# UPCNSL-ABS-EPS_test-v1_0.net
KiCad netlist of a schematic drawn in Altium Designer
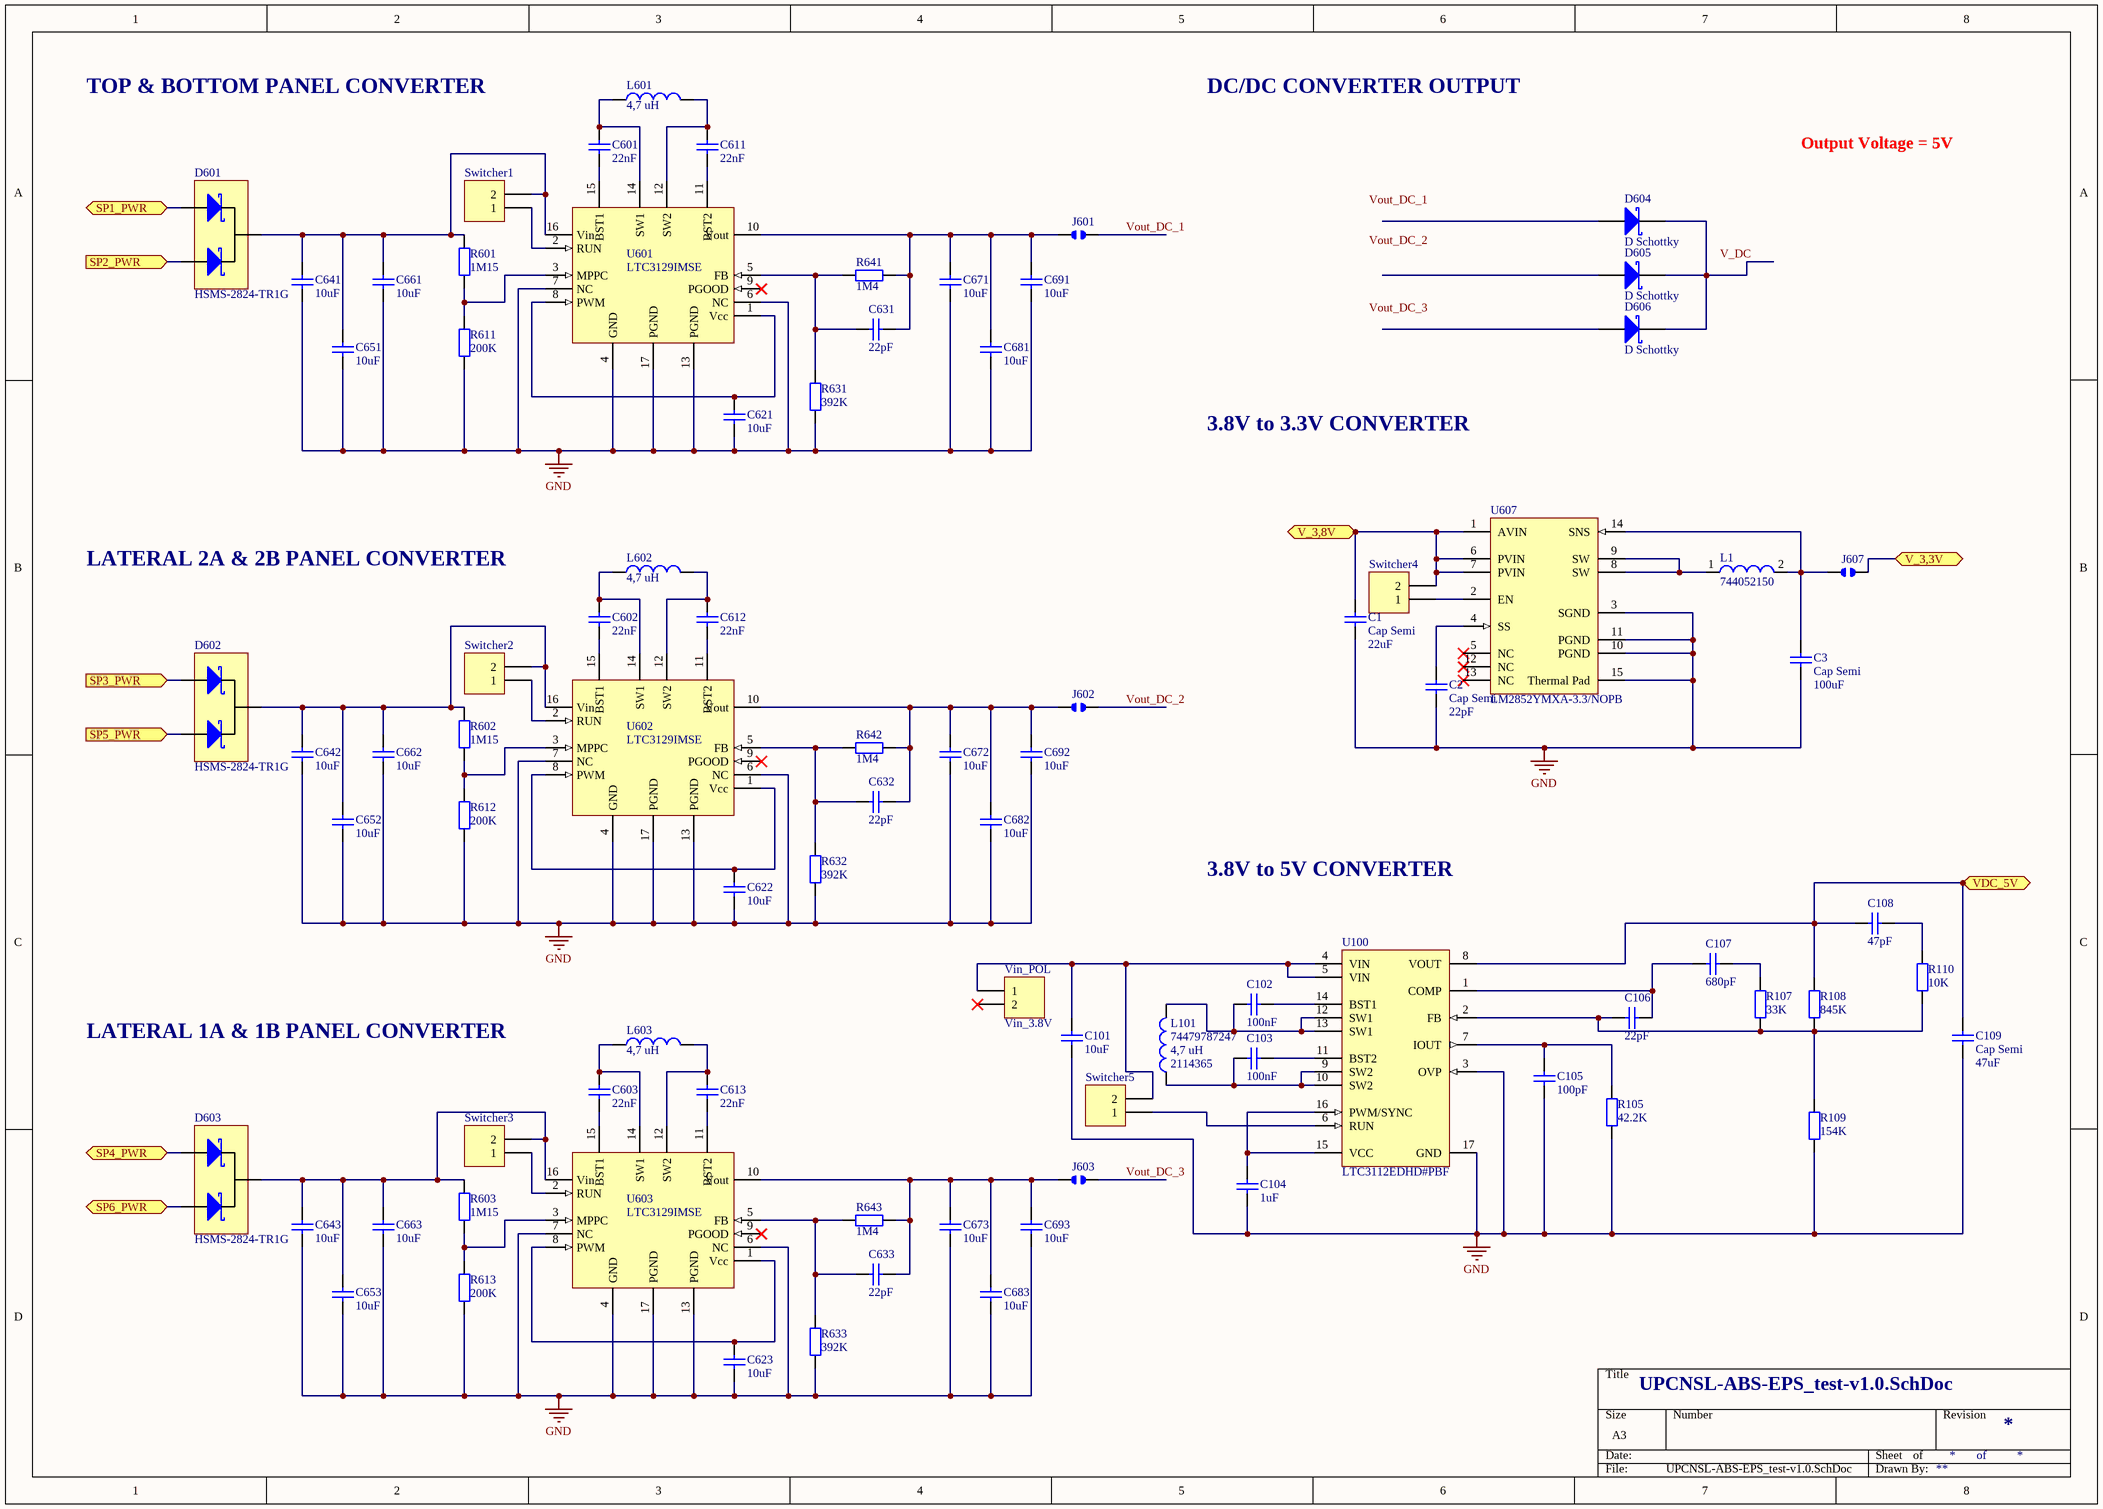
[diagram p0: UPCNSL-ABS-EPS_test-v1.0.SchDoc]

(export (version "E")
  (design (tool "Eeschema 10.0.6"))
  (components
    (comp (ref "C1")
      (value "Cap Semi")
      (footprint "C1206")
      (description "Capacitor (Semiconductor SIM Model)")
      (fields (field (name "ALTIUM_VALUE") "22uF") (field (name "PUBLISHER") "Altium Limited"))
      (libsource (lib "Miscellaneous Devices") (part "Cap Semi"))
    )
    (comp (ref "C2")
      (value "Cap Semi")
      (footprint "1608[0603]")
      (description "Capacitor (Semiconductor SIM Model)")
      (fields (field (name "ALTIUM_VALUE") "22pF") (field (name "PUBLISHER") "Altium Limited"))
      (libsource (lib "Miscellaneous Devices") (part "Cap Semi"))
    )
    (comp (ref "C3")
      (value "Cap Semi")
      (footprint "C1206")
      (description "Capacitor (Semiconductor SIM Model)")
      (fields (field (name "ALTIUM_VALUE") "100uF") (field (name "PUBLISHER") "Altium Limited"))
      (libsource (lib "Miscellaneous Devices") (part "Cap Semi"))
    )
    (comp (ref "C101")
      (value "10uF")
      (footprint "CAP0603")
      (description "Capacitor")
      (fields (field (name "Comment") "CAP0603"))
      (libsource (lib "EPS") (part "CAP0603"))
    )
    (comp (ref "C102")
      (value "100nF")
      (footprint "CAP0603")
      (description "Capacitor")
      (fields (field (name "Comment") "CAP0603"))
      (libsource (lib "EPS") (part "CAP0603"))
    )
    (comp (ref "C103")
      (value "100nF")
      (footprint "CAP0603")
      (description "Capacitor")
      (fields (field (name "Comment") "CAP0603"))
      (libsource (lib "EPS") (part "CAP0603"))
    )
    (comp (ref "C104")
      (value "1uF")
      (footprint "CAP0603")
      (description "Capacitor")
      (fields (field (name "Comment") "CAP0603"))
      (libsource (lib "EPS") (part "CAP0603"))
    )
    (comp (ref "C105")
      (value "100pF")
      (footprint "CAP0603")
      (description "Capacitor")
      (fields (field (name "Comment") "CAP0603"))
      (libsource (lib "EPS") (part "CAP0603"))
    )
    (comp (ref "C106")
      (value "22pF")
      (footprint "CAP0603")
      (description "Capacitor")
      (fields (field (name "Comment") "CAP0603"))
      (libsource (lib "EPS") (part "CAP0603"))
    )
    (comp (ref "C107")
      (value "680pF")
      (footprint "CAP0603")
      (description "Capacitor")
      (fields (field (name "Comment") "CAP0603"))
      (libsource (lib "EPS") (part "CAP0603"))
    )
    (comp (ref "C108")
      (value "47pF")
      (footprint "CAP0603")
      (description "Capacitor")
      (fields (field (name "Comment") "CAP0603"))
      (libsource (lib "EPS") (part "CAP0603"))
    )
    (comp (ref "C109")
      (value "Cap Semi")
      (footprint "C1206")
      (description "Capacitor (Semiconductor SIM Model)")
      (fields (field (name "ALTIUM_VALUE") "47uF") (field (name "PUBLISHER") "Altium Limited"))
      (libsource (lib "Miscellaneous Devices") (part "Cap Semi"))
    )
    (comp (ref "C601")
      (value "22nF")
      (footprint "CAP0603")
      (description "Capacitor")
      (fields (field (name "Comment") "CAP0603"))
      (libsource (lib "EPS") (part "CAP0603"))
    )
    (comp (ref "C602")
      (value "22nF")
      (footprint "CAP0603")
      (description "Capacitor")
      (fields (field (name "Comment") "CAP0603"))
      (libsource (lib "EPS") (part "CAP0603"))
    )
    (comp (ref "C603")
      (value "22nF")
      (footprint "CAP0603")
      (description "Capacitor")
      (fields (field (name "Comment") "CAP0603"))
      (libsource (lib "EPS") (part "CAP0603"))
    )
    (comp (ref "C611")
      (value "22nF")
      (footprint "CAP0603")
      (description "Capacitor")
      (fields (field (name "Comment") "CAP0603"))
      (libsource (lib "EPS") (part "CAP0603"))
    )
    (comp (ref "C612")
      (value "22nF")
      (footprint "CAP0603")
      (description "Capacitor")
      (fields (field (name "Comment") "CAP0603"))
      (libsource (lib "EPS") (part "CAP0603"))
    )
    (comp (ref "C613")
      (value "22nF")
      (footprint "CAP0603")
      (description "Capacitor")
      (fields (field (name "Comment") "CAP0603"))
      (libsource (lib "EPS") (part "CAP0603"))
    )
    (comp (ref "C621")
      (value "10uF")
      (footprint "CAP0603")
      (description "Capacitor")
      (fields (field (name "Comment") "CAP0603"))
      (libsource (lib "EPS") (part "CAP0603"))
    )
    (comp (ref "C622")
      (value "10uF")
      (footprint "CAP0603")
      (description "Capacitor")
      (fields (field (name "Comment") "CAP0603"))
      (libsource (lib "EPS") (part "CAP0603"))
    )
    (comp (ref "C623")
      (value "10uF")
      (footprint "CAP0603")
      (description "Capacitor")
      (fields (field (name "Comment") "CAP0603"))
      (libsource (lib "EPS") (part "CAP0603"))
    )
    (comp (ref "C631")
      (value "22pF")
      (footprint "CAP0603")
      (description "Capacitor")
      (fields (field (name "Comment") "CAP0603"))
      (libsource (lib "EPS") (part "CAP0603"))
    )
    (comp (ref "C632")
      (value "22pF")
      (footprint "CAP0603")
      (description "Capacitor")
      (fields (field (name "Comment") "CAP0603"))
      (libsource (lib "EPS") (part "CAP0603"))
    )
    (comp (ref "C633")
      (value "22pF")
      (footprint "CAP0603")
      (description "Capacitor")
      (fields (field (name "Comment") "CAP0603"))
      (libsource (lib "EPS") (part "CAP0603"))
    )
    (comp (ref "C641")
      (value "10uF")
      (footprint "CAP0603")
      (description "Capacitor")
      (fields (field (name "Comment") "CAP0603"))
      (libsource (lib "EPS") (part "CAP0603"))
    )
    (comp (ref "C642")
      (value "10uF")
      (footprint "CAP0603")
      (description "Capacitor")
      (fields (field (name "Comment") "CAP0603"))
      (libsource (lib "EPS") (part "CAP0603"))
    )
    (comp (ref "C643")
      (value "10uF")
      (footprint "CAP0603")
      (description "Capacitor")
      (fields (field (name "Comment") "CAP0603"))
      (libsource (lib "EPS") (part "CAP0603"))
    )
    (comp (ref "C651")
      (value "10uF")
      (footprint "CAP0603")
      (description "Capacitor")
      (fields (field (name "Comment") "CAP0603"))
      (libsource (lib "EPS") (part "CAP0603"))
    )
    (comp (ref "C652")
      (value "10uF")
      (footprint "CAP0603")
      (description "Capacitor")
      (fields (field (name "Comment") "CAP0603"))
      (libsource (lib "EPS") (part "CAP0603"))
    )
    (comp (ref "C653")
      (value "10uF")
      (footprint "CAP0603")
      (description "Capacitor")
      (fields (field (name "Comment") "CAP0603"))
      (libsource (lib "EPS") (part "CAP0603"))
    )
    (comp (ref "C661")
      (value "10uF")
      (footprint "CAP0603")
      (description "Capacitor")
      (fields (field (name "Comment") "CAP0603"))
      (libsource (lib "EPS") (part "CAP0603"))
    )
    (comp (ref "C662")
      (value "10uF")
      (footprint "CAP0603")
      (description "Capacitor")
      (fields (field (name "Comment") "CAP0603"))
      (libsource (lib "EPS") (part "CAP0603"))
    )
    (comp (ref "C663")
      (value "10uF")
      (footprint "CAP0603")
      (description "Capacitor")
      (fields (field (name "Comment") "CAP0603"))
      (libsource (lib "EPS") (part "CAP0603"))
    )
    (comp (ref "C671")
      (value "10uF")
      (footprint "CAP0603")
      (description "Capacitor")
      (fields (field (name "Comment") "CAP0603"))
      (libsource (lib "EPS") (part "CAP0603"))
    )
    (comp (ref "C672")
      (value "10uF")
      (footprint "CAP0603")
      (description "Capacitor")
      (fields (field (name "Comment") "CAP0603"))
      (libsource (lib "EPS") (part "CAP0603"))
    )
    (comp (ref "C673")
      (value "10uF")
      (footprint "CAP0603")
      (description "Capacitor")
      (fields (field (name "Comment") "CAP0603"))
      (libsource (lib "EPS") (part "CAP0603"))
    )
    (comp (ref "C681")
      (value "10uF")
      (footprint "CAP0603")
      (description "Capacitor")
      (fields (field (name "Comment") "CAP0603"))
      (libsource (lib "EPS") (part "CAP0603"))
    )
    (comp (ref "C682")
      (value "10uF")
      (footprint "CAP0603")
      (description "Capacitor")
      (fields (field (name "Comment") "CAP0603"))
      (libsource (lib "EPS") (part "CAP0603"))
    )
    (comp (ref "C683")
      (value "10uF")
      (footprint "CAP0603")
      (description "Capacitor")
      (fields (field (name "Comment") "CAP0603"))
      (libsource (lib "EPS") (part "CAP0603"))
    )
    (comp (ref "C691")
      (value "10uF")
      (footprint "CAP0603")
      (description "Capacitor")
      (fields (field (name "Comment") "CAP0603"))
      (libsource (lib "EPS") (part "CAP0603"))
    )
    (comp (ref "C692")
      (value "10uF")
      (footprint "CAP0603")
      (description "Capacitor")
      (fields (field (name "Comment") "CAP0603"))
      (libsource (lib "EPS") (part "CAP0603"))
    )
    (comp (ref "C693")
      (value "10uF")
      (footprint "CAP0603")
      (description "Capacitor")
      (fields (field (name "Comment") "CAP0603"))
      (libsource (lib "EPS") (part "CAP0603"))
    )
    (comp (ref "D601")
      (value "HSMS-2824-TR1G")
      (footprint "SOT23-3")
      (description "DIODE, RF, SCHOTTKY, DUAL, SOT-23")
      (libsource (lib "EPS") (part "HSMS-2824-TR1G"))
    )
    (comp (ref "D602")
      (value "HSMS-2824-TR1G")
      (footprint "SOT23-3")
      (description "DIODE, RF, SCHOTTKY, DUAL, SOT-23")
      (libsource (lib "EPS") (part "HSMS-2824-TR1G"))
    )
    (comp (ref "D603")
      (value "HSMS-2824-TR1G")
      (footprint "SOT23-3")
      (description "DIODE, RF, SCHOTTKY, DUAL, SOT-23")
      (libsource (lib "EPS") (part "HSMS-2824-TR1G"))
    )
    (comp (ref "D604")
      (value "D Schottky")
      (footprint "SMB")
      (description "Schottky Diode")
      (fields (field (name "PUBLISHER") "Altium Limited"))
      (libsource (lib "Miscellaneous Devices") (part "D Schottky"))
    )
    (comp (ref "D605")
      (value "D Schottky")
      (footprint "SMB")
      (description "Schottky Diode")
      (fields (field (name "PUBLISHER") "Altium Limited"))
      (libsource (lib "Miscellaneous Devices") (part "D Schottky"))
    )
    (comp (ref "D606")
      (value "D Schottky")
      (footprint "SMB")
      (description "Schottky Diode")
      (fields (field (name "PUBLISHER") "Altium Limited"))
      (libsource (lib "Miscellaneous Devices") (part "D Schottky"))
    )
    (comp (ref "J601")
      (value "Jumper_Solderpad")
      (footprint "JUMPER_SOLDERPAD")
      (libsource (lib "EPS") (part "Jumper_Solderpad"))
    )
    (comp (ref "J602")
      (value "Jumper_Solderpad")
      (footprint "JUMPER_SOLDERPAD")
      (libsource (lib "EPS") (part "Jumper_Solderpad"))
    )
    (comp (ref "J603")
      (value "Jumper_Solderpad")
      (footprint "JUMPER_SOLDERPAD")
      (libsource (lib "EPS") (part "Jumper_Solderpad"))
    )
    (comp (ref "J607")
      (value "~")
      (footprint "JUMPER_SOLDERPAD")
      (description "Jumper_Solderpad")
      (libsource (lib "EPS") (part "Jumper_Solderpad"))
    )
    (comp (ref "L1")
      (value "744052150")
      (footprint "WE-TPC-5818-L")
      (description "SMD Shielded Tiny Power Inductor WE-TPC, L = 15.0 µH")
      (libsource (lib "WE-TPC SMD Shielded Tiny Power Inductor") (part "744052150"))
    )
    (comp (ref "L101")
      (value "74479787247")
      (footprint "74479787247")
      (description "INDUCTOR, 4.7UH, 1.25A, 40MHZ")
      (fields (field (name "ALTIUM_VALUE") "4,7 uH") (field (name "SUPPLIER PART NUMBER 1") "2114365"))
      (libsource (lib "EPS") (part "74479787247"))
    )
    (comp (ref "L601")
      (value "4,7 uH")
      (footprint "74479787247")
      (description "INDUCTOR, 4.7UH, 1.25A, 40MHZ")
      (libsource (lib "EPS") (part "74479787247"))
    )
    (comp (ref "L602")
      (value "4,7 uH")
      (footprint "74479787247")
      (description "INDUCTOR, 4.7UH, 1.25A, 40MHZ")
      (libsource (lib "EPS") (part "74479787247"))
    )
    (comp (ref "L603")
      (value "4,7 uH")
      (footprint "74479787247")
      (description "INDUCTOR, 4.7UH, 1.25A, 40MHZ")
      (libsource (lib "EPS") (part "74479787247"))
    )
    (comp (ref "R105")
      (value "42.2K")
      (footprint "RES0603")
      (description "Resistor")
      (fields (field (name "Comment") "RES0603"))
      (libsource (lib "EPS") (part "RES0603"))
    )
    (comp (ref "R107")
      (value "33K")
      (footprint "RES0603")
      (description "Resistor")
      (fields (field (name "Comment") "RES0603"))
      (libsource (lib "EPS") (part "RES0603"))
    )
    (comp (ref "R108")
      (value "845K")
      (footprint "RES0603")
      (description "Resistor")
      (fields (field (name "Comment") "RES0603"))
      (libsource (lib "EPS") (part "RES0603"))
    )
    (comp (ref "R109")
      (value "154K")
      (footprint "RES0603")
      (description "Resistor")
      (fields (field (name "Comment") "RES0603"))
      (libsource (lib "EPS") (part "RES0603"))
    )
    (comp (ref "R110")
      (value "10K")
      (footprint "RES0603")
      (description "Resistor")
      (fields (field (name "Comment") "RES0603"))
      (libsource (lib "EPS") (part "RES0603"))
    )
    (comp (ref "R601")
      (value "1M15")
      (footprint "RES0603")
      (description "Resistor")
      (fields (field (name "Comment") "RES0603"))
      (libsource (lib "EPS") (part "RES0603"))
    )
    (comp (ref "R602")
      (value "1M15")
      (footprint "RES0603")
      (description "Resistor")
      (fields (field (name "Comment") "RES0603"))
      (libsource (lib "EPS") (part "RES0603"))
    )
    (comp (ref "R603")
      (value "1M15")
      (footprint "RES0603")
      (description "Resistor")
      (fields (field (name "Comment") "RES0603"))
      (libsource (lib "EPS") (part "RES0603"))
    )
    (comp (ref "R611")
      (value "200K")
      (footprint "RES0603")
      (description "Resistor")
      (fields (field (name "Comment") "RES0603"))
      (libsource (lib "EPS") (part "RES0603"))
    )
    (comp (ref "R612")
      (value "200K")
      (footprint "RES0603")
      (description "Resistor")
      (fields (field (name "Comment") "RES0603"))
      (libsource (lib "EPS") (part "RES0603"))
    )
    (comp (ref "R613")
      (value "200K")
      (footprint "RES0603")
      (description "Resistor")
      (fields (field (name "Comment") "RES0603"))
      (libsource (lib "EPS") (part "RES0603"))
    )
    (comp (ref "R631")
      (value "392K")
      (footprint "RES0603")
      (description "Resistor")
      (fields (field (name "Comment") "RES0603"))
      (libsource (lib "EPS") (part "RES0603"))
    )
    (comp (ref "R632")
      (value "392K")
      (footprint "RES0603")
      (description "Resistor")
      (fields (field (name "Comment") "RES0603"))
      (libsource (lib "EPS") (part "RES0603"))
    )
    (comp (ref "R633")
      (value "392K")
      (footprint "RES0603")
      (description "Resistor")
      (fields (field (name "Comment") "RES0603"))
      (libsource (lib "EPS") (part "RES0603"))
    )
    (comp (ref "R641")
      (value "1M4")
      (footprint "RES0603")
      (description "Resistor")
      (fields (field (name "Comment") "RES0603"))
      (libsource (lib "") (part "RES0603_1"))
    )
    (comp (ref "R642")
      (value "1M4")
      (footprint "RES0603")
      (description "Resistor")
      (fields (field (name "Comment") "RES0603"))
      (libsource (lib "") (part "RES0603_1"))
    )
    (comp (ref "R643")
      (value "1M4")
      (footprint "RES0603")
      (description "Resistor")
      (fields (field (name "Comment") "RES0603"))
      (libsource (lib "") (part "RES0603_1"))
    )
    (comp (ref "Switcher1")
      (value "~")
      (footprint "HDR1X2")
      (description "Header, 2-Pin")
      (fields (field (name "PUBLISHER") "Altium Limited"))
      (libsource (lib "Miscellaneous Connectors") (part "Header 2"))
    )
    (comp (ref "Switcher2")
      (value "~")
      (footprint "HDR1X2")
      (description "Header, 2-Pin")
      (fields (field (name "PUBLISHER") "Altium Limited"))
      (libsource (lib "Miscellaneous Connectors") (part "Header 2"))
    )
    (comp (ref "Switcher3")
      (value "~")
      (footprint "HDR1X2")
      (description "Header, 2-Pin")
      (fields (field (name "PUBLISHER") "Altium Limited"))
      (libsource (lib "Miscellaneous Connectors") (part "Header 2"))
    )
    (comp (ref "Switcher4")
      (value "~")
      (footprint "HDR1X2")
      (description "Header, 2-Pin")
      (fields (field (name "PUBLISHER") "Altium Limited"))
      (libsource (lib "Miscellaneous Connectors") (part "Header 2"))
    )
    (comp (ref "Switcher5")
      (value "~")
      (footprint "HDR1X2")
      (description "Header, 2-Pin")
      (fields (field (name "PUBLISHER") "Altium Limited"))
      (libsource (lib "Miscellaneous Connectors") (part "Header 2"))
    )
    (comp (ref "U100")
      (value "LTC3112EDHD#PBF")
      (footprint "LT-DHD-16_V")
      (description "2.5 A Synchronous Buck-Boost DC/DC Converter, 16-pin SON (DHD-16), -40 to 125 degC, Pb-Free")
      (fields (field (name "MANUFACTURER") "Linear Technology"))
      (libsource (lib "Linear Technology Power Management Switching Regulator LTC1174-LTC3901") (part "LTC3112EDHD#PBF"))
    )
    (comp (ref "U601")
      (value "LTC3129IMSE")
      (footprint "MSOP-16")
      (description "15V, 200mA Synchronous Buck-Boost DC/DC Converter with 1.3µA Quiescent Current")
      (libsource (lib "EPS") (part "LTC3129"))
    )
    (comp (ref "U602")
      (value "LTC3129IMSE")
      (footprint "MSOP-16")
      (description "15V, 200mA Synchronous Buck-Boost DC/DC Converter with 1.3µA Quiescent Current")
      (libsource (lib "EPS") (part "LTC3129"))
    )
    (comp (ref "U603")
      (value "LTC3129IMSE")
      (footprint "MSOP-16")
      (description "15V, 200mA Synchronous Buck-Boost DC/DC Converter with 1.3µA Quiescent Current")
      (libsource (lib "EPS") (part "LTC3129"))
    )
    (comp (ref "U607")
      (value "LM2852YMXA-3.3/NOPB")
      (footprint "MXA14A_L")
      (description "2A 500/1500kHz Synchronous SIMPLE SWITCHER® Buck Regulator, 14-pin TSSOP-EP, Pb-Free")
      (fields (field (name "MANUFACTURER") "National Semiconductor"))
      (libsource (lib "Switcher") (part "LM2852YMXA-3.3/NOPB"))
    )
    (comp (ref "Vin_POL")
      (value "Vin_3.8V")
      (footprint "HDR1X2")
      (description "Header, 2-Pin")
      (fields (field (name "PUBLISHER") "Altium Limited"))
      (libsource (lib "") (part "Header 2_1"))
    )
  )
  (nets
    (net (code "1") (name "/SP1_PWR") (class "Default")
      (node (ref "D601") (pin "1") (pinfunction "A1_1") (pintype "passive"))
    )
    (net (code "2") (name "/SP2_PWR") (class "Default")
      (node (ref "D601") (pin "2") (pinfunction "A2_2") (pintype "passive"))
    )
    (net (code "3") (name "/SP3_PWR") (class "Default")
      (node (ref "D602") (pin "1") (pinfunction "A1_1") (pintype "passive"))
    )
    (net (code "4") (name "/SP4_PWR") (class "Default")
      (node (ref "D603") (pin "1") (pinfunction "A1_1") (pintype "passive"))
    )
    (net (code "5") (name "/SP5_PWR") (class "Default")
      (node (ref "D602") (pin "2") (pinfunction "A2_2") (pintype "passive"))
    )
    (net (code "6") (name "/SP6_PWR") (class "Default")
      (node (ref "D603") (pin "2") (pinfunction "A2_2") (pintype "passive"))
    )
    (net (code "7") (name "/VDC_5V") (class "Default")
      (node (ref "C108") (pin "1") (pinfunction "1_1") (pintype "passive"))
      (node (ref "C109") (pin "1") (pinfunction "1_1") (pintype "passive"))
      (node (ref "R108") (pin "2") (pinfunction "2_2") (pintype "passive"))
      (node (ref "U100") (pin "8") (pinfunction "VOUT_8") (pintype "power_in"))
    )
    (net (code "8") (name "/V_3,3V") (class "Default")
      (node (ref "J607") (pin "2") (pinfunction "2_2") (pintype "passive"))
    )
    (net (code "9") (name "/V_3,8V") (class "Default")
      (node (ref "C1") (pin "1") (pinfunction "1_1") (pintype "passive"))
      (node (ref "Switcher4") (pin "2") (pinfunction "2_2") (pintype "passive"))
      (node (ref "U607") (pin "1") (pinfunction "AVIN_1") (pintype "power_in"))
      (node (ref "U607") (pin "6") (pinfunction "PVIN_6") (pintype "power_in"))
      (node (ref "U607") (pin "7") (pinfunction "PVIN_7") (pintype "power_in"))
    )
    (net (code "11") (name "/Vout_DC_1") (class "Default")
      (node (ref "J601") (pin "2") (pinfunction "2_2") (pintype "passive"))
    )
    (net (code "12") (name "/Vout_DC_2") (class "Default")
      (node (ref "J602") (pin "2") (pinfunction "2_2") (pintype "passive"))
    )
    (net (code "13") (name "/Vout_DC_3") (class "Default")
      (node (ref "J603") (pin "2") (pinfunction "2_2") (pintype "passive"))
    )
    (net (code "14") (name "GND") (class "Default")
      (node (ref "C1") (pin "2") (pinfunction "2_2") (pintype "passive"))
      (node (ref "C101") (pin "1") (pinfunction "1_1") (pintype "passive"))
      (node (ref "C104") (pin "1") (pinfunction "1_1") (pintype "passive"))
      (node (ref "C105") (pin "1") (pinfunction "1_1") (pintype "passive"))
      (node (ref "C109") (pin "2") (pinfunction "2_2") (pintype "passive"))
      (node (ref "C2") (pin "2") (pinfunction "2_2") (pintype "passive"))
      (node (ref "C3") (pin "2") (pinfunction "2_2") (pintype "passive"))
      (node (ref "C621") (pin "1") (pinfunction "1_1") (pintype "passive"))
      (node (ref "C622") (pin "1") (pinfunction "1_1") (pintype "passive"))
      (node (ref "C623") (pin "1") (pinfunction "1_1") (pintype "passive"))
      (node (ref "C641") (pin "1") (pinfunction "1_1") (pintype "passive"))
      (node (ref "C642") (pin "1") (pinfunction "1_1") (pintype "passive"))
      (node (ref "C643") (pin "1") (pinfunction "1_1") (pintype "passive"))
      (node (ref "C651") (pin "1") (pinfunction "1_1") (pintype "passive"))
      (node (ref "C652") (pin "1") (pinfunction "1_1") (pintype "passive"))
      (node (ref "C653") (pin "1") (pinfunction "1_1") (pintype "passive"))
      (node (ref "C661") (pin "1") (pinfunction "1_1") (pintype "passive"))
      (node (ref "C662") (pin "1") (pinfunction "1_1") (pintype "passive"))
      (node (ref "C663") (pin "1") (pinfunction "1_1") (pintype "passive"))
      (node (ref "C671") (pin "1") (pinfunction "1_1") (pintype "passive"))
      (node (ref "C672") (pin "1") (pinfunction "1_1") (pintype "passive"))
      (node (ref "C673") (pin "1") (pinfunction "1_1") (pintype "passive"))
      (node (ref "C681") (pin "1") (pinfunction "1_1") (pintype "passive"))
      (node (ref "C682") (pin "1") (pinfunction "1_1") (pintype "passive"))
      (node (ref "C683") (pin "1") (pinfunction "1_1") (pintype "passive"))
      (node (ref "C691") (pin "1") (pinfunction "1_1") (pintype "passive"))
      (node (ref "C692") (pin "1") (pinfunction "1_1") (pintype "passive"))
      (node (ref "C693") (pin "1") (pinfunction "1_1") (pintype "passive"))
      (node (ref "R105") (pin "1") (pinfunction "1_1") (pintype "passive"))
      (node (ref "R109") (pin "1") (pinfunction "1_1") (pintype "passive"))
      (node (ref "R611") (pin "1") (pinfunction "1_1") (pintype "passive"))
      (node (ref "R612") (pin "1") (pinfunction "1_1") (pintype "passive"))
      (node (ref "R613") (pin "1") (pinfunction "1_1") (pintype "passive"))
      (node (ref "R631") (pin "1") (pinfunction "1_1") (pintype "passive"))
      (node (ref "R632") (pin "1") (pinfunction "1_1") (pintype "passive"))
      (node (ref "R633") (pin "1") (pinfunction "1_1") (pintype "passive"))
      (node (ref "U100") (pin "17") (pinfunction "GND_17") (pintype "power_in"))
      (node (ref "U100") (pin "3") (pinfunction "OVP_3") (pintype "input"))
      (node (ref "U601") (pin "13") (pinfunction "PGND_13") (pintype "power_in"))
      (node (ref "U601") (pin "17") (pinfunction "PGND_17") (pintype "power_in"))
      (node (ref "U601") (pin "4") (pinfunction "GND_4") (pintype "power_in"))
      (node (ref "U601") (pin "6") (pinfunction "NC_6") (pintype "passive"))
      (node (ref "U601") (pin "7") (pinfunction "NC_7") (pintype "passive"))
      (node (ref "U602") (pin "13") (pinfunction "PGND_13") (pintype "power_in"))
      (node (ref "U602") (pin "17") (pinfunction "PGND_17") (pintype "power_in"))
      (node (ref "U602") (pin "4") (pinfunction "GND_4") (pintype "power_in"))
      (node (ref "U602") (pin "6") (pinfunction "NC_6") (pintype "passive"))
      (node (ref "U602") (pin "7") (pinfunction "NC_7") (pintype "passive"))
      (node (ref "U603") (pin "13") (pinfunction "PGND_13") (pintype "power_in"))
      (node (ref "U603") (pin "17") (pinfunction "PGND_17") (pintype "power_in"))
      (node (ref "U603") (pin "4") (pinfunction "GND_4") (pintype "power_in"))
      (node (ref "U603") (pin "6") (pinfunction "NC_6") (pintype "passive"))
      (node (ref "U603") (pin "7") (pinfunction "NC_7") (pintype "passive"))
      (node (ref "U607") (pin "10") (pinfunction "PGND_10") (pintype "power_in"))
      (node (ref "U607") (pin "11") (pinfunction "PGND_11") (pintype "power_in"))
      (node (ref "U607") (pin "15") (pinfunction "Thermal_Pad_15") (pintype "power_in"))
      (node (ref "U607") (pin "3") (pinfunction "SGND_3") (pintype "power_in"))
    )
    (net (code "15") (name "Net-(C101-Pad2)") (class "Default")
      (node (ref "C101") (pin "2") (pinfunction "2_2") (pintype "passive"))
      (node (ref "Switcher5") (pin "2") (pinfunction "2_2") (pintype "passive"))
      (node (ref "U100") (pin "4") (pinfunction "VIN_4") (pintype "power_in"))
      (node (ref "U100") (pin "5") (pinfunction "VIN_5") (pintype "power_in"))
      (node (ref "Vin_POL") (pin "1") (pinfunction "1_1") (pintype "passive"))
    )
    (net (code "16") (name "Net-(C102-Pad2)") (class "Default")
      (node (ref "C102") (pin "2") (pinfunction "2_2") (pintype "passive"))
      (node (ref "L101") (pin "2") (pinfunction "2_2") (pintype "passive"))
      (node (ref "U100") (pin "12") (pinfunction "SW1_12") (pintype "passive"))
      (node (ref "U100") (pin "13") (pinfunction "SW1_13") (pintype "passive"))
    )
    (net (code "17") (name "Net-(C103-Pad2)") (class "Default")
      (node (ref "C103") (pin "2") (pinfunction "2_2") (pintype "passive"))
      (node (ref "L101") (pin "1") (pinfunction "1_1") (pintype "passive"))
      (node (ref "U100") (pin "10") (pinfunction "SW2_10") (pintype "passive"))
      (node (ref "U100") (pin "9") (pinfunction "SW2_9") (pintype "passive"))
    )
    (net (code "18") (name "Net-(C107-Pad2)") (class "Default")
      (node (ref "C107") (pin "2") (pinfunction "2_2") (pintype "passive"))
      (node (ref "R107") (pin "2") (pinfunction "2_2") (pintype "passive"))
    )
    (net (code "19") (name "Net-(C108-Pad2)") (class "Default")
      (node (ref "C108") (pin "2") (pinfunction "2_2") (pintype "passive"))
      (node (ref "R110") (pin "2") (pinfunction "2_2") (pintype "passive"))
    )
    (net (code "20") (name "Net-(D601-K)") (class "Default")
      (node (ref "C641") (pin "2") (pinfunction "2_2") (pintype "passive"))
      (node (ref "C651") (pin "2") (pinfunction "2_2") (pintype "passive"))
      (node (ref "C661") (pin "2") (pinfunction "2_2") (pintype "passive"))
      (node (ref "D601") (pin "3") (pinfunction "K_3") (pintype "passive"))
      (node (ref "R601") (pin "2") (pinfunction "2_2") (pintype "passive"))
      (node (ref "Switcher1") (pin "2") (pinfunction "2_2") (pintype "passive"))
      (node (ref "U601") (pin "16") (pinfunction "Vin_16") (pintype "power_in"))
    )
    (net (code "21") (name "Net-(D602-K)") (class "Default")
      (node (ref "C642") (pin "2") (pinfunction "2_2") (pintype "passive"))
      (node (ref "C652") (pin "2") (pinfunction "2_2") (pintype "passive"))
      (node (ref "C662") (pin "2") (pinfunction "2_2") (pintype "passive"))
      (node (ref "D602") (pin "3") (pinfunction "K_3") (pintype "passive"))
      (node (ref "R602") (pin "2") (pinfunction "2_2") (pintype "passive"))
      (node (ref "Switcher2") (pin "2") (pinfunction "2_2") (pintype "passive"))
      (node (ref "U602") (pin "16") (pinfunction "Vin_16") (pintype "power_in"))
    )
    (net (code "22") (name "Net-(D603-K)") (class "Default")
      (node (ref "C643") (pin "2") (pinfunction "2_2") (pintype "passive"))
      (node (ref "C653") (pin "2") (pinfunction "2_2") (pintype "passive"))
      (node (ref "C663") (pin "2") (pinfunction "2_2") (pintype "passive"))
      (node (ref "D603") (pin "3") (pinfunction "K_3") (pintype "passive"))
      (node (ref "R603") (pin "2") (pinfunction "2_2") (pintype "passive"))
      (node (ref "Switcher3") (pin "2") (pinfunction "2_2") (pintype "passive"))
      (node (ref "U603") (pin "16") (pinfunction "Vin_16") (pintype "power_in"))
    )
    (net (code "23") (name "Net-(D604-K)") (class "Default")
      (node (ref "D604") (pin "2") (pinfunction "K_2") (pintype "passive"))
      (node (ref "D605") (pin "2") (pinfunction "K_2") (pintype "passive"))
      (node (ref "D606") (pin "2") (pinfunction "K_2") (pintype "passive"))
    )
    (net (code "24") (name "Net-(L1-Pad1)") (class "Default")
      (node (ref "L1") (pin "1") (pinfunction "1_1") (pintype "passive"))
      (node (ref "U607") (pin "8") (pinfunction "SW_8") (pintype "power_in"))
      (node (ref "U607") (pin "9") (pinfunction "SW_9") (pintype "power_in"))
    )
    (net (code "25") (name "Net-(U100-BST1)") (class "Default")
      (node (ref "C102") (pin "1") (pinfunction "1_1") (pintype "passive"))
      (node (ref "U100") (pin "14") (pinfunction "BST1_14") (pintype "passive"))
    )
    (net (code "26") (name "Net-(U100-BST2)") (class "Default")
      (node (ref "C103") (pin "1") (pinfunction "1_1") (pintype "passive"))
      (node (ref "U100") (pin "11") (pinfunction "BST2_11") (pintype "passive"))
    )
    (net (code "27") (name "Net-(U100-COMP)") (class "Default")
      (node (ref "C106") (pin "2") (pinfunction "2_2") (pintype "passive"))
      (node (ref "C107") (pin "1") (pinfunction "1_1") (pintype "passive"))
      (node (ref "U100") (pin "1") (pinfunction "COMP_1") (pintype "passive"))
    )
    (net (code "28") (name "Net-(U100-FB)") (class "Default")
      (node (ref "C106") (pin "1") (pinfunction "1_1") (pintype "passive"))
      (node (ref "R107") (pin "1") (pinfunction "1_1") (pintype "passive"))
      (node (ref "R108") (pin "1") (pinfunction "1_1") (pintype "passive"))
      (node (ref "R109") (pin "2") (pinfunction "2_2") (pintype "passive"))
      (node (ref "R110") (pin "1") (pinfunction "1_1") (pintype "passive"))
      (node (ref "U100") (pin "2") (pinfunction "FB_2") (pintype "input"))
    )
    (net (code "29") (name "Net-(U100-IOUT)") (class "Default")
      (node (ref "C105") (pin "2") (pinfunction "2_2") (pintype "passive"))
      (node (ref "R105") (pin "2") (pinfunction "2_2") (pintype "passive"))
      (node (ref "U100") (pin "7") (pinfunction "IOUT_7") (pintype "output"))
    )
    (net (code "30") (name "Net-(U100-PWM{slash}SYNC)") (class "Default")
      (node (ref "C104") (pin "2") (pinfunction "2_2") (pintype "passive"))
      (node (ref "U100") (pin "15") (pinfunction "VCC_15") (pintype "power_in"))
      (node (ref "U100") (pin "16") (pinfunction "PWM/SYNC_16") (pintype "input"))
    )
    (net (code "31") (name "Net-(U100-RUN)") (class "Default")
      (node (ref "Switcher5") (pin "1") (pinfunction "1_1") (pintype "passive"))
      (node (ref "U100") (pin "6") (pinfunction "RUN_6") (pintype "input"))
    )
    (net (code "32") (name "Net-(U601-BST1)") (class "Default")
      (node (ref "C601") (pin "1") (pinfunction "1_1") (pintype "passive"))
      (node (ref "U601") (pin "15") (pinfunction "BST1_15") (pintype "power_in"))
    )
    (net (code "33") (name "Net-(U601-BST2)") (class "Default")
      (node (ref "C611") (pin "1") (pinfunction "1_1") (pintype "passive"))
      (node (ref "U601") (pin "11") (pinfunction "BST2_11") (pintype "power_in"))
    )
    (net (code "34") (name "Net-(U601-FB)") (class "Default")
      (node (ref "C631") (pin "2") (pinfunction "2_2") (pintype "passive"))
      (node (ref "R631") (pin "2") (pinfunction "2_2") (pintype "passive"))
      (node (ref "R641") (pin "2") (pinfunction "2_2") (pintype "passive"))
      (node (ref "U601") (pin "5") (pinfunction "FB_5") (pintype "input"))
    )
    (net (code "35") (name "Net-(U601-MPPC)") (class "Default")
      (node (ref "R601") (pin "1") (pinfunction "1_1") (pintype "passive"))
      (node (ref "R611") (pin "2") (pinfunction "2_2") (pintype "passive"))
      (node (ref "U601") (pin "3") (pinfunction "MPPC_3") (pintype "input"))
    )
    (net (code "36") (name "Net-(U601-PWM)") (class "Default")
      (node (ref "C621") (pin "2") (pinfunction "2_2") (pintype "passive"))
      (node (ref "U601") (pin "1") (pinfunction "Vcc_1") (pintype "power_in"))
      (node (ref "U601") (pin "8") (pinfunction "PWM_8") (pintype "input"))
    )
    (net (code "37") (name "Net-(U601-RUN)") (class "Default")
      (node (ref "Switcher1") (pin "1") (pinfunction "1_1") (pintype "passive"))
      (node (ref "U601") (pin "2") (pinfunction "RUN_2") (pintype "input"))
    )
    (net (code "38") (name "Net-(U601-SW1)") (class "Default")
      (node (ref "C601") (pin "2") (pinfunction "2_2") (pintype "passive"))
      (node (ref "L601") (pin "1") (pinfunction "1_1") (pintype "passive"))
      (node (ref "U601") (pin "14") (pinfunction "SW1_14") (pintype "power_in"))
    )
    (net (code "39") (name "Net-(U601-SW2)") (class "Default")
      (node (ref "C611") (pin "2") (pinfunction "2_2") (pintype "passive"))
      (node (ref "L601") (pin "2") (pinfunction "2_2") (pintype "passive"))
      (node (ref "U601") (pin "12") (pinfunction "SW2_12") (pintype "power_in"))
    )
    (net (code "40") (name "Net-(U601-Vout)") (class "Default")
      (node (ref "C631") (pin "1") (pinfunction "1_1") (pintype "passive"))
      (node (ref "C671") (pin "2") (pinfunction "2_2") (pintype "passive"))
      (node (ref "C681") (pin "2") (pinfunction "2_2") (pintype "passive"))
      (node (ref "C691") (pin "2") (pinfunction "2_2") (pintype "passive"))
      (node (ref "J601") (pin "1") (pinfunction "1_1") (pintype "passive"))
      (node (ref "R641") (pin "1") (pinfunction "1_1") (pintype "passive"))
      (node (ref "U601") (pin "10") (pinfunction "Vout_10") (pintype "power_in"))
    )
    (net (code "41") (name "Net-(U602-BST1)") (class "Default")
      (node (ref "C602") (pin "1") (pinfunction "1_1") (pintype "passive"))
      (node (ref "U602") (pin "15") (pinfunction "BST1_15") (pintype "power_in"))
    )
    (net (code "42") (name "Net-(U602-BST2)") (class "Default")
      (node (ref "C612") (pin "1") (pinfunction "1_1") (pintype "passive"))
      (node (ref "U602") (pin "11") (pinfunction "BST2_11") (pintype "power_in"))
    )
    (net (code "43") (name "Net-(U602-FB)") (class "Default")
      (node (ref "C632") (pin "2") (pinfunction "2_2") (pintype "passive"))
      (node (ref "R632") (pin "2") (pinfunction "2_2") (pintype "passive"))
      (node (ref "R642") (pin "2") (pinfunction "2_2") (pintype "passive"))
      (node (ref "U602") (pin "5") (pinfunction "FB_5") (pintype "input"))
    )
    (net (code "44") (name "Net-(U602-MPPC)") (class "Default")
      (node (ref "R602") (pin "1") (pinfunction "1_1") (pintype "passive"))
      (node (ref "R612") (pin "2") (pinfunction "2_2") (pintype "passive"))
      (node (ref "U602") (pin "3") (pinfunction "MPPC_3") (pintype "input"))
    )
    (net (code "45") (name "Net-(U602-PWM)") (class "Default")
      (node (ref "C622") (pin "2") (pinfunction "2_2") (pintype "passive"))
      (node (ref "U602") (pin "1") (pinfunction "Vcc_1") (pintype "power_in"))
      (node (ref "U602") (pin "8") (pinfunction "PWM_8") (pintype "input"))
    )
    (net (code "46") (name "Net-(U602-RUN)") (class "Default")
      (node (ref "Switcher2") (pin "1") (pinfunction "1_1") (pintype "passive"))
      (node (ref "U602") (pin "2") (pinfunction "RUN_2") (pintype "input"))
    )
    (net (code "47") (name "Net-(U602-SW1)") (class "Default")
      (node (ref "C602") (pin "2") (pinfunction "2_2") (pintype "passive"))
      (node (ref "L602") (pin "1") (pinfunction "1_1") (pintype "passive"))
      (node (ref "U602") (pin "14") (pinfunction "SW1_14") (pintype "power_in"))
    )
    (net (code "48") (name "Net-(U602-SW2)") (class "Default")
      (node (ref "C612") (pin "2") (pinfunction "2_2") (pintype "passive"))
      (node (ref "L602") (pin "2") (pinfunction "2_2") (pintype "passive"))
      (node (ref "U602") (pin "12") (pinfunction "SW2_12") (pintype "power_in"))
    )
    (net (code "49") (name "Net-(U602-Vout)") (class "Default")
      (node (ref "C632") (pin "1") (pinfunction "1_1") (pintype "passive"))
      (node (ref "C672") (pin "2") (pinfunction "2_2") (pintype "passive"))
      (node (ref "C682") (pin "2") (pinfunction "2_2") (pintype "passive"))
      (node (ref "C692") (pin "2") (pinfunction "2_2") (pintype "passive"))
      (node (ref "J602") (pin "1") (pinfunction "1_1") (pintype "passive"))
      (node (ref "R642") (pin "1") (pinfunction "1_1") (pintype "passive"))
      (node (ref "U602") (pin "10") (pinfunction "Vout_10") (pintype "power_in"))
    )
    (net (code "50") (name "Net-(U603-BST1)") (class "Default")
      (node (ref "C603") (pin "1") (pinfunction "1_1") (pintype "passive"))
      (node (ref "U603") (pin "15") (pinfunction "BST1_15") (pintype "power_in"))
    )
    (net (code "51") (name "Net-(U603-BST2)") (class "Default")
      (node (ref "C613") (pin "1") (pinfunction "1_1") (pintype "passive"))
      (node (ref "U603") (pin "11") (pinfunction "BST2_11") (pintype "power_in"))
    )
    (net (code "52") (name "Net-(U603-FB)") (class "Default")
      (node (ref "C633") (pin "2") (pinfunction "2_2") (pintype "passive"))
      (node (ref "R633") (pin "2") (pinfunction "2_2") (pintype "passive"))
      (node (ref "R643") (pin "2") (pinfunction "2_2") (pintype "passive"))
      (node (ref "U603") (pin "5") (pinfunction "FB_5") (pintype "input"))
    )
    (net (code "53") (name "Net-(U603-MPPC)") (class "Default")
      (node (ref "R603") (pin "1") (pinfunction "1_1") (pintype "passive"))
      (node (ref "R613") (pin "2") (pinfunction "2_2") (pintype "passive"))
      (node (ref "U603") (pin "3") (pinfunction "MPPC_3") (pintype "input"))
    )
    (net (code "54") (name "Net-(U603-PWM)") (class "Default")
      (node (ref "C623") (pin "2") (pinfunction "2_2") (pintype "passive"))
      (node (ref "U603") (pin "1") (pinfunction "Vcc_1") (pintype "power_in"))
      (node (ref "U603") (pin "8") (pinfunction "PWM_8") (pintype "input"))
    )
    (net (code "55") (name "Net-(U603-RUN)") (class "Default")
      (node (ref "Switcher3") (pin "1") (pinfunction "1_1") (pintype "passive"))
      (node (ref "U603") (pin "2") (pinfunction "RUN_2") (pintype "input"))
    )
    (net (code "56") (name "Net-(U603-SW1)") (class "Default")
      (node (ref "C603") (pin "2") (pinfunction "2_2") (pintype "passive"))
      (node (ref "L603") (pin "1") (pinfunction "1_1") (pintype "passive"))
      (node (ref "U603") (pin "14") (pinfunction "SW1_14") (pintype "power_in"))
    )
    (net (code "57") (name "Net-(U603-SW2)") (class "Default")
      (node (ref "C613") (pin "2") (pinfunction "2_2") (pintype "passive"))
      (node (ref "L603") (pin "2") (pinfunction "2_2") (pintype "passive"))
      (node (ref "U603") (pin "12") (pinfunction "SW2_12") (pintype "power_in"))
    )
    (net (code "58") (name "Net-(U603-Vout)") (class "Default")
      (node (ref "C633") (pin "1") (pinfunction "1_1") (pintype "passive"))
      (node (ref "C673") (pin "2") (pinfunction "2_2") (pintype "passive"))
      (node (ref "C683") (pin "2") (pinfunction "2_2") (pintype "passive"))
      (node (ref "C693") (pin "2") (pinfunction "2_2") (pintype "passive"))
      (node (ref "J603") (pin "1") (pinfunction "1_1") (pintype "passive"))
      (node (ref "R643") (pin "1") (pinfunction "1_1") (pintype "passive"))
      (node (ref "U603") (pin "10") (pinfunction "Vout_10") (pintype "power_in"))
    )
    (net (code "59") (name "Net-(U607-EN)") (class "Default")
      (node (ref "Switcher4") (pin "1") (pinfunction "1_1") (pintype "passive"))
      (node (ref "U607") (pin "2") (pinfunction "EN_2") (pintype "passive"))
    )
    (net (code "60") (name "Net-(U607-SNS)") (class "Default")
      (node (ref "C3") (pin "1") (pinfunction "1_1") (pintype "passive"))
      (node (ref "J607") (pin "1") (pinfunction "1_1") (pintype "passive"))
      (node (ref "L1") (pin "2") (pinfunction "2_2") (pintype "passive"))
      (node (ref "U607") (pin "14") (pinfunction "SNS_14") (pintype "input"))
    )
    (net (code "61") (name "Net-(U607-SS)") (class "Default")
      (node (ref "C2") (pin "1") (pinfunction "1_1") (pintype "passive"))
      (node (ref "U607") (pin "4") (pinfunction "SS_4") (pintype "input"))
    )
    (net (code "62") (name "unconnected-(D604-A-Pad1)") (class "Default")
      (node (ref "D604") (pin "1") (pinfunction "A_1") (pintype "passive"))
    )
    (net (code "63") (name "unconnected-(D605-A-Pad1)") (class "Default")
      (node (ref "D605") (pin "1") (pinfunction "A_1") (pintype "passive"))
    )
    (net (code "64") (name "unconnected-(D606-A-Pad1)") (class "Default")
      (node (ref "D606") (pin "1") (pinfunction "A_1") (pintype "passive"))
    )
    (net (code "65") (name "unconnected-(U601-PGOOD-Pad9)") (class "Default")
      (node (ref "U601") (pin "9") (pinfunction "PGOOD_9") (pintype "input+no_connect"))
    )
    (net (code "66") (name "unconnected-(U602-PGOOD-Pad9)") (class "Default")
      (node (ref "U602") (pin "9") (pinfunction "PGOOD_9") (pintype "input+no_connect"))
    )
    (net (code "67") (name "unconnected-(U603-PGOOD-Pad9)") (class "Default")
      (node (ref "U603") (pin "9") (pinfunction "PGOOD_9") (pintype "input+no_connect"))
    )
    (net (code "68") (name "unconnected-(U607-NC-Pad5)") (class "Default")
      (node (ref "U607") (pin "5") (pinfunction "NC_5") (pintype "passive+no_connect"))
    )
    (net (code "69") (name "unconnected-(U607-NC-Pad12)") (class "Default")
      (node (ref "U607") (pin "12") (pinfunction "NC_12") (pintype "passive+no_connect"))
    )
    (net (code "70") (name "unconnected-(U607-NC-Pad13)") (class "Default")
      (node (ref "U607") (pin "13") (pinfunction "NC_13") (pintype "passive+no_connect"))
    )
    (net (code "71") (name "unconnected-(Vin_POL-Pad2)") (class "Default")
      (node (ref "Vin_POL") (pin "2") (pinfunction "2_2") (pintype "passive+no_connect"))
    )
  )
)
